# Board_4_Buttons_WS-TASV.net
KiCad netlist of a schematic drawn in EAGLE
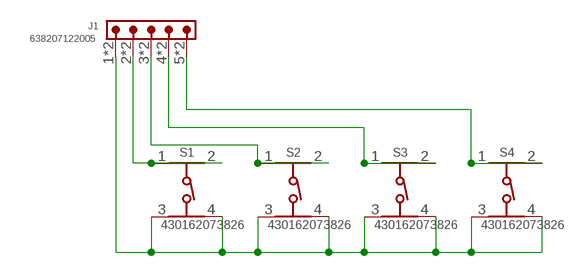
[diagram p0: schematic, sheet 1]

(export (version "E")
  (design (tool "Eeschema 10.0.6"))
  (components
    (comp (ref "J1")
      (value "638207122005")
      (footprint "eagle-import:638207122005")
      (libsource (lib "eagle-import") (part "638207122005"))
    )
    (comp (ref "S1")
      (value "430162073826")
      (footprint "eagle-import:430162073826")
      (libsource (lib "eagle-import") (part "430162073826"))
    )
    (comp (ref "S2")
      (value "430162073826")
      (footprint "eagle-import:430162073826")
      (libsource (lib "eagle-import") (part "430162073826"))
    )
    (comp (ref "S3")
      (value "430162073826")
      (footprint "eagle-import:430162073826")
      (libsource (lib "eagle-import") (part "430162073826"))
    )
    (comp (ref "S4")
      (value "430162073826")
      (footprint "eagle-import:430162073826")
      (libsource (lib "eagle-import") (part "430162073826"))
    )
  )
  (nets
    (net (code "1") (name "Net-(S1-2)") (class "Default")
      (node (ref "J1") (pin "1") (pinfunction "1_1") (pintype "passive"))
      (node (ref "J1") (pin "A1") (pinfunction "1_A1") (pintype "passive"))
      (node (ref "S1") (pin "3") (pinfunction "2_3") (pintype "passive"))
      (node (ref "S1") (pin "4") (pinfunction "4_4") (pintype "passive"))
      (node (ref "S2") (pin "3") (pinfunction "2_3") (pintype "passive"))
      (node (ref "S2") (pin "4") (pinfunction "4_4") (pintype "passive"))
      (node (ref "S3") (pin "3") (pinfunction "2_3") (pintype "passive"))
      (node (ref "S3") (pin "4") (pinfunction "4_4") (pintype "passive"))
      (node (ref "S4") (pin "3") (pinfunction "2_3") (pintype "passive"))
      (node (ref "S4") (pin "4") (pinfunction "4_4") (pintype "passive"))
    )
    (net (code "2") (name "Net-(S1-3)") (class "Default")
      (node (ref "J1") (pin "2") (pinfunction "2_2") (pintype "passive"))
      (node (ref "J1") (pin "A2") (pinfunction "2_A2") (pintype "passive"))
      (node (ref "S1") (pin "1") (pinfunction "1_1") (pintype "passive"))
      (node (ref "S1") (pin "2") (pinfunction "3_2") (pintype "passive"))
    )
    (net (code "3") (name "Net-(S2-3)") (class "Default")
      (node (ref "J1") (pin "3") (pinfunction "3_3") (pintype "passive"))
      (node (ref "J1") (pin "A3") (pinfunction "3_A3") (pintype "passive"))
      (node (ref "S2") (pin "1") (pinfunction "1_1") (pintype "passive"))
      (node (ref "S2") (pin "2") (pinfunction "3_2") (pintype "passive"))
    )
    (net (code "4") (name "Net-(S3-3)") (class "Default")
      (node (ref "J1") (pin "4") (pinfunction "4_4") (pintype "passive"))
      (node (ref "J1") (pin "A4") (pinfunction "4_A4") (pintype "passive"))
      (node (ref "S3") (pin "1") (pinfunction "1_1") (pintype "passive"))
      (node (ref "S3") (pin "2") (pinfunction "3_2") (pintype "passive"))
    )
    (net (code "5") (name "Net-(S4-3)") (class "Default")
      (node (ref "J1") (pin "5") (pinfunction "5_5") (pintype "passive"))
      (node (ref "J1") (pin "A5") (pinfunction "5_A5") (pintype "passive"))
      (node (ref "S4") (pin "1") (pinfunction "1_1") (pintype "passive"))
      (node (ref "S4") (pin "2") (pinfunction "3_2") (pintype "passive"))
    )
  )
)
